# redbear.net
KiCad netlist of a schematic drawn in EAGLE
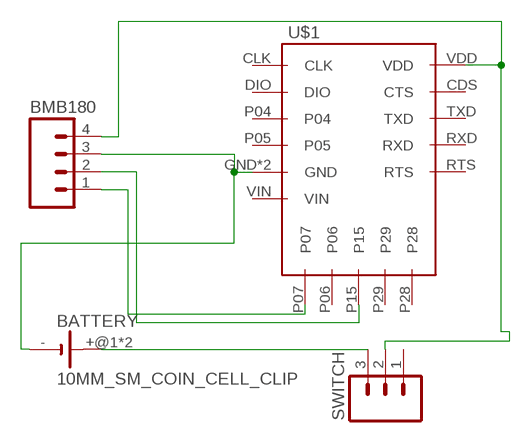
[diagram p0: schematic, sheet 1]

(export (version "E")
  (design (tool "Eeschema 10.0.6"))
  (components
    (comp (ref "BATTERY")
      (value "10MM_SM_COIN_CELL_CLIP")
      (footprint "eagle-import:10MM_SM_COIN_CELL_CLIP")
      (libsource (lib "eagle-import") (part "10MM_SM_COIN_CELL_CLIP"))
    )
    (comp (ref "BMB180")
      (value "M04NO_SILK_ALL_ROUND")
      (footprint "eagle-import:1X04_NO_SILK_ALL_ROUND")
      (libsource (lib "eagle-import") (part "M04NO_SILK_ALL_ROUND"))
    )
    (comp (ref "SWITCH")
      (value "M03PTH")
      (footprint "eagle-import:1X03")
      (libsource (lib "eagle-import") (part "M03PTH"))
    )
    (comp (ref "U$1")
      (value "REDBEAR_NANOBREAKOUT1")
      (footprint "eagle-import:BREAKOUT")
      (libsource (lib "eagle-import") (part "REDBEAR_NANOBREAKOUT1"))
    )
  )
  (nets
    (net (code "1") (name "Net-(BATTERY-+-Pad+@1)") (class "Default")
      (node (ref "BATTERY") (pin "+@1") (pinfunction "+_+@1") (pintype "passive"))
      (node (ref "BATTERY") (pin "+@2") (pinfunction "+_+@2") (pintype "passive"))
      (node (ref "SWITCH") (pin "3") (pinfunction "3_3") (pintype "passive"))
    )
    (net (code "2") (name "Net-(BATTERY-Pad-)") (class "Default")
      (node (ref "BATTERY") (pin "-") (pinfunction "-_-") (pintype "passive"))
      (node (ref "BMB180") (pin "3") (pinfunction "3_3") (pintype "passive"))
      (node (ref "U$1") (pin "GND") (pinfunction "GND_GND") (pintype "bidirectional"))
      (node (ref "U$1") (pin "GND1") (pinfunction "GND_GND1") (pintype "bidirectional"))
    )
    (net (code "3") (name "Net-(BMB180-Pad1)") (class "Default")
      (node (ref "BMB180") (pin "1") (pinfunction "1_1") (pintype "passive"))
      (node (ref "U$1") (pin "P07") (pinfunction "P07_P07") (pintype "bidirectional"))
    )
    (net (code "4") (name "Net-(BMB180-Pad2)") (class "Default")
      (node (ref "BMB180") (pin "2") (pinfunction "2_2") (pintype "passive"))
      (node (ref "U$1") (pin "P15") (pinfunction "P15_P15") (pintype "bidirectional"))
    )
    (net (code "5") (name "Net-(BMB180-Pad4)") (class "Default")
      (node (ref "BMB180") (pin "4") (pinfunction "4_4") (pintype "passive"))
      (node (ref "SWITCH") (pin "2") (pinfunction "2_2") (pintype "passive"))
      (node (ref "U$1") (pin "VDD") (pinfunction "VDD_VDD") (pintype "bidirectional"))
    )
    (net (code "6") (name "unconnected-(SWITCH-Pad1)") (class "Default")
      (node (ref "SWITCH") (pin "1") (pinfunction "1_1") (pintype "passive"))
    )
    (net (code "7") (name "unconnected-(U$1-CTS-PadCDS)") (class "Default")
      (node (ref "U$1") (pin "CDS") (pinfunction "CTS_CDS") (pintype "bidirectional"))
    )
    (net (code "8") (name "unconnected-(U$1-PadCLK)") (class "Default")
      (node (ref "U$1") (pin "CLK") (pinfunction "CLK_CLK") (pintype "bidirectional"))
    )
    (net (code "9") (name "unconnected-(U$1-PadDIO)") (class "Default")
      (node (ref "U$1") (pin "DIO") (pinfunction "DIO_DIO") (pintype "bidirectional"))
    )
    (net (code "10") (name "unconnected-(U$1-PadP04)") (class "Default")
      (node (ref "U$1") (pin "P04") (pinfunction "P04_P04") (pintype "bidirectional"))
    )
    (net (code "11") (name "unconnected-(U$1-PadP05)") (class "Default")
      (node (ref "U$1") (pin "P05") (pinfunction "P05_P05") (pintype "bidirectional"))
    )
    (net (code "12") (name "unconnected-(U$1-PadP06)") (class "Default")
      (node (ref "U$1") (pin "P06") (pinfunction "P06_P06") (pintype "bidirectional"))
    )
    (net (code "13") (name "unconnected-(U$1-PadP28)") (class "Default")
      (node (ref "U$1") (pin "P28") (pinfunction "P28_P28") (pintype "bidirectional"))
    )
    (net (code "14") (name "unconnected-(U$1-PadP29)") (class "Default")
      (node (ref "U$1") (pin "P29") (pinfunction "P29_P29") (pintype "bidirectional"))
    )
    (net (code "15") (name "unconnected-(U$1-PadRTS)") (class "Default")
      (node (ref "U$1") (pin "RTS") (pinfunction "RTS_RTS") (pintype "bidirectional"))
    )
    (net (code "16") (name "unconnected-(U$1-PadRXD)") (class "Default")
      (node (ref "U$1") (pin "RXD") (pinfunction "RXD_RXD") (pintype "bidirectional"))
    )
    (net (code "17") (name "unconnected-(U$1-PadTXD)") (class "Default")
      (node (ref "U$1") (pin "TXD") (pinfunction "TXD_TXD") (pintype "bidirectional"))
    )
    (net (code "18") (name "unconnected-(U$1-PadVIN)") (class "Default")
      (node (ref "U$1") (pin "VIN") (pinfunction "VIN_VIN") (pintype "bidirectional"))
    )
  )
)
